# TETHER_CONNECTOR.net
KiCad netlist of a schematic drawn in Altium Designer
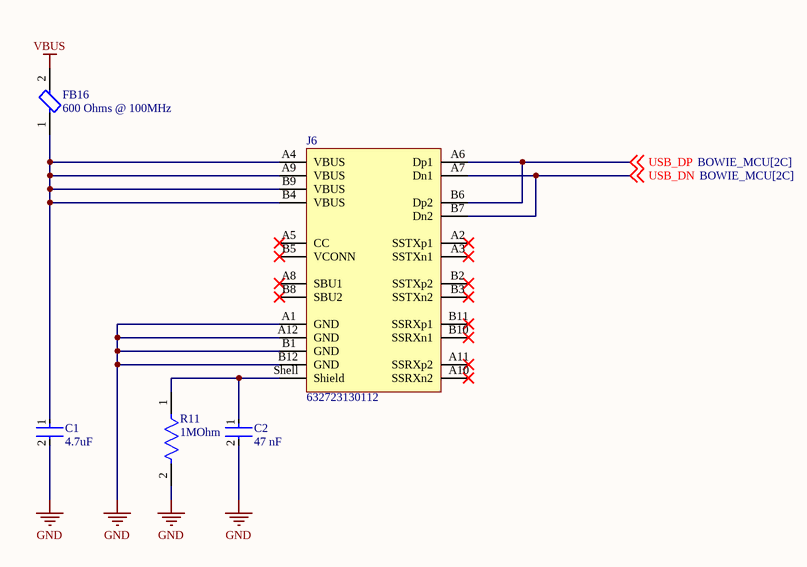
[diagram p0: TETHER_CONNECTOR.SchDoc]

(export (version "E")
  (design (tool "Eeschema 10.0.6"))
  (components
    (comp (ref "C1")
      (value "4.7uF")
      (footprint "FP-CL828-IPC_C")
      (description "Cap Ceramic 4.7uF 10V X5R ±10% SMD 0402 +85°C Paper T/R")
      (fields (field (name "TOLERANCE") "10%"))
      (libsource (lib "Altium Content Vault") (part "b4654b650e69147ec39a6b967a45e02"))
    )
    (comp (ref "C2")
      (value "47 nF")
      (footprint "FP-CC0402-MFG")
      (description "CAP CER 0.047UF 25V X7R 0402")
      (fields
        (field (name "MANUFACTURER PART NUMBER") "CC0402KRX7R8BB473")
        (field (name "MANUFACTURER") "YAGEO")
      )
      (libsource (lib "Altium Content Vault") (part "11868f565c42a9108669ba33697ecf6"))
    )
    (comp (ref "FB16")
      (value "600 Ohms @ 100MHz")
      (footprint "FP-BLM15-0_05-MFG")
      (description "Chip Ferrite Bead, 0402, 600Ω @ 100MHz, 0.23Ω, 25%, 900mA")
      (fields (field (name "TOLERANCE") "25%"))
      (libsource (lib "Altium Content Vault") (part "5f30dd21d616792df468990f7003faa"))
    )
    (comp (ref "J6")
      (value "632723130112")
      (footprint "632723130112")
      (description "WR-COM_USB 3.1_TYPE C_HORIZONTAL")
      (libsource (lib "Altium Content Vault") (part "USB 3.1_Type C_Receptacle_1 Port"))
    )
    (comp (ref "R11")
      (value "1MOhm")
      (footprint "FP-RMCF0402-MFG")
      (description "1MΩ ±1% 0.063W 0402 Thick Film Chip Resistor AEC-Q200 compliant")
      (fields (field (name "TOLERANCE") "1%"))
      (libsource (lib "Altium Content Vault") (part "1029c3af85768c4190bb7ad29bc67b5"))
    )
  )
  (nets
    (net (code "1") (name "GND") (class "Default")
      (node (ref "C1") (pin "2") (pinfunction "2_2") (pintype "passive"))
      (node (ref "C2") (pin "2") (pinfunction "2_2") (pintype "passive"))
      (node (ref "J6") (pin "A1") (pinfunction "GND_A1") (pintype "passive"))
      (node (ref "J6") (pin "A12") (pinfunction "GND_A12") (pintype "passive"))
      (node (ref "J6") (pin "B1") (pinfunction "GND_B1") (pintype "passive"))
      (node (ref "J6") (pin "B12") (pinfunction "GND_B12") (pintype "passive"))
      (node (ref "R11") (pin "2") (pinfunction "2_2") (pintype "passive"))
    )
    (net (code "2") (name "Net-(C1-Pad1)") (class "Default")
      (node (ref "C1") (pin "1") (pinfunction "1_1") (pintype "passive"))
      (node (ref "FB16") (pin "1") (pinfunction "1_1") (pintype "passive"))
      (node (ref "J6") (pin "A4") (pinfunction "VBUS_A4") (pintype "passive"))
      (node (ref "J6") (pin "A9") (pinfunction "VBUS_A9") (pintype "passive"))
      (node (ref "J6") (pin "B4") (pinfunction "VBUS_B4") (pintype "passive"))
      (node (ref "J6") (pin "B9") (pinfunction "VBUS_B9") (pintype "passive"))
    )
    (net (code "3") (name "Net-(J6-Shield)") (class "Default")
      (node (ref "C2") (pin "1") (pinfunction "1_1") (pintype "passive"))
      (node (ref "J6") (pin "Shell") (pinfunction "Shield_Shell") (pintype "passive"))
      (node (ref "R11") (pin "1") (pinfunction "1_1") (pintype "passive"))
    )
    (net (code "4") (name "USB_DN") (class "Default")
      (node (ref "J6") (pin "A7") (pinfunction "Dn1_A7") (pintype "passive"))
      (node (ref "J6") (pin "B7") (pinfunction "Dn2_B7") (pintype "passive"))
    )
    (net (code "5") (name "USB_DP") (class "Default")
      (node (ref "J6") (pin "A6") (pinfunction "Dp1_A6") (pintype "passive"))
      (node (ref "J6") (pin "B6") (pinfunction "Dp2_B6") (pintype "passive"))
    )
    (net (code "6") (name "VBUS") (class "Default")
      (node (ref "FB16") (pin "2") (pinfunction "2_2") (pintype "passive"))
    )
    (net (code "7") (name "unconnected-(J6-CC-PadA5)") (class "Default")
      (node (ref "J6") (pin "A5") (pinfunction "CC_A5") (pintype "passive+no_connect"))
    )
    (net (code "8") (name "unconnected-(J6-SBU1-PadA8)") (class "Default")
      (node (ref "J6") (pin "A8") (pinfunction "SBU1_A8") (pintype "passive+no_connect"))
    )
    (net (code "9") (name "unconnected-(J6-SBU2-PadB8)") (class "Default")
      (node (ref "J6") (pin "B8") (pinfunction "SBU2_B8") (pintype "passive+no_connect"))
    )
    (net (code "10") (name "unconnected-(J6-SSRXn1-PadB10)") (class "Default")
      (node (ref "J6") (pin "B10") (pinfunction "SSRXn1_B10") (pintype "passive+no_connect"))
    )
    (net (code "11") (name "unconnected-(J6-SSRXn2-PadA10)") (class "Default")
      (node (ref "J6") (pin "A10") (pinfunction "SSRXn2_A10") (pintype "passive+no_connect"))
    )
    (net (code "12") (name "unconnected-(J6-SSRXp1-PadB11)") (class "Default")
      (node (ref "J6") (pin "B11") (pinfunction "SSRXp1_B11") (pintype "passive+no_connect"))
    )
    (net (code "13") (name "unconnected-(J6-SSRXp2-PadA11)") (class "Default")
      (node (ref "J6") (pin "A11") (pinfunction "SSRXp2_A11") (pintype "passive+no_connect"))
    )
    (net (code "14") (name "unconnected-(J6-SSTXn1-PadA3)") (class "Default")
      (node (ref "J6") (pin "A3") (pinfunction "SSTXn1_A3") (pintype "passive+no_connect"))
    )
    (net (code "15") (name "unconnected-(J6-SSTXn2-PadB3)") (class "Default")
      (node (ref "J6") (pin "B3") (pinfunction "SSTXn2_B3") (pintype "passive+no_connect"))
    )
    (net (code "16") (name "unconnected-(J6-SSTXp1-PadA2)") (class "Default")
      (node (ref "J6") (pin "A2") (pinfunction "SSTXp1_A2") (pintype "passive+no_connect"))
    )
    (net (code "17") (name "unconnected-(J6-SSTXp2-PadB2)") (class "Default")
      (node (ref "J6") (pin "B2") (pinfunction "SSTXp2_B2") (pintype "passive+no_connect"))
    )
    (net (code "18") (name "unconnected-(J6-VCONN-PadB5)") (class "Default")
      (node (ref "J6") (pin "B5") (pinfunction "VCONN_B5") (pintype "passive+no_connect"))
    )
  )
)
